# CCM_0020_revC.net
KiCad netlist of a schematic drawn in EAGLE
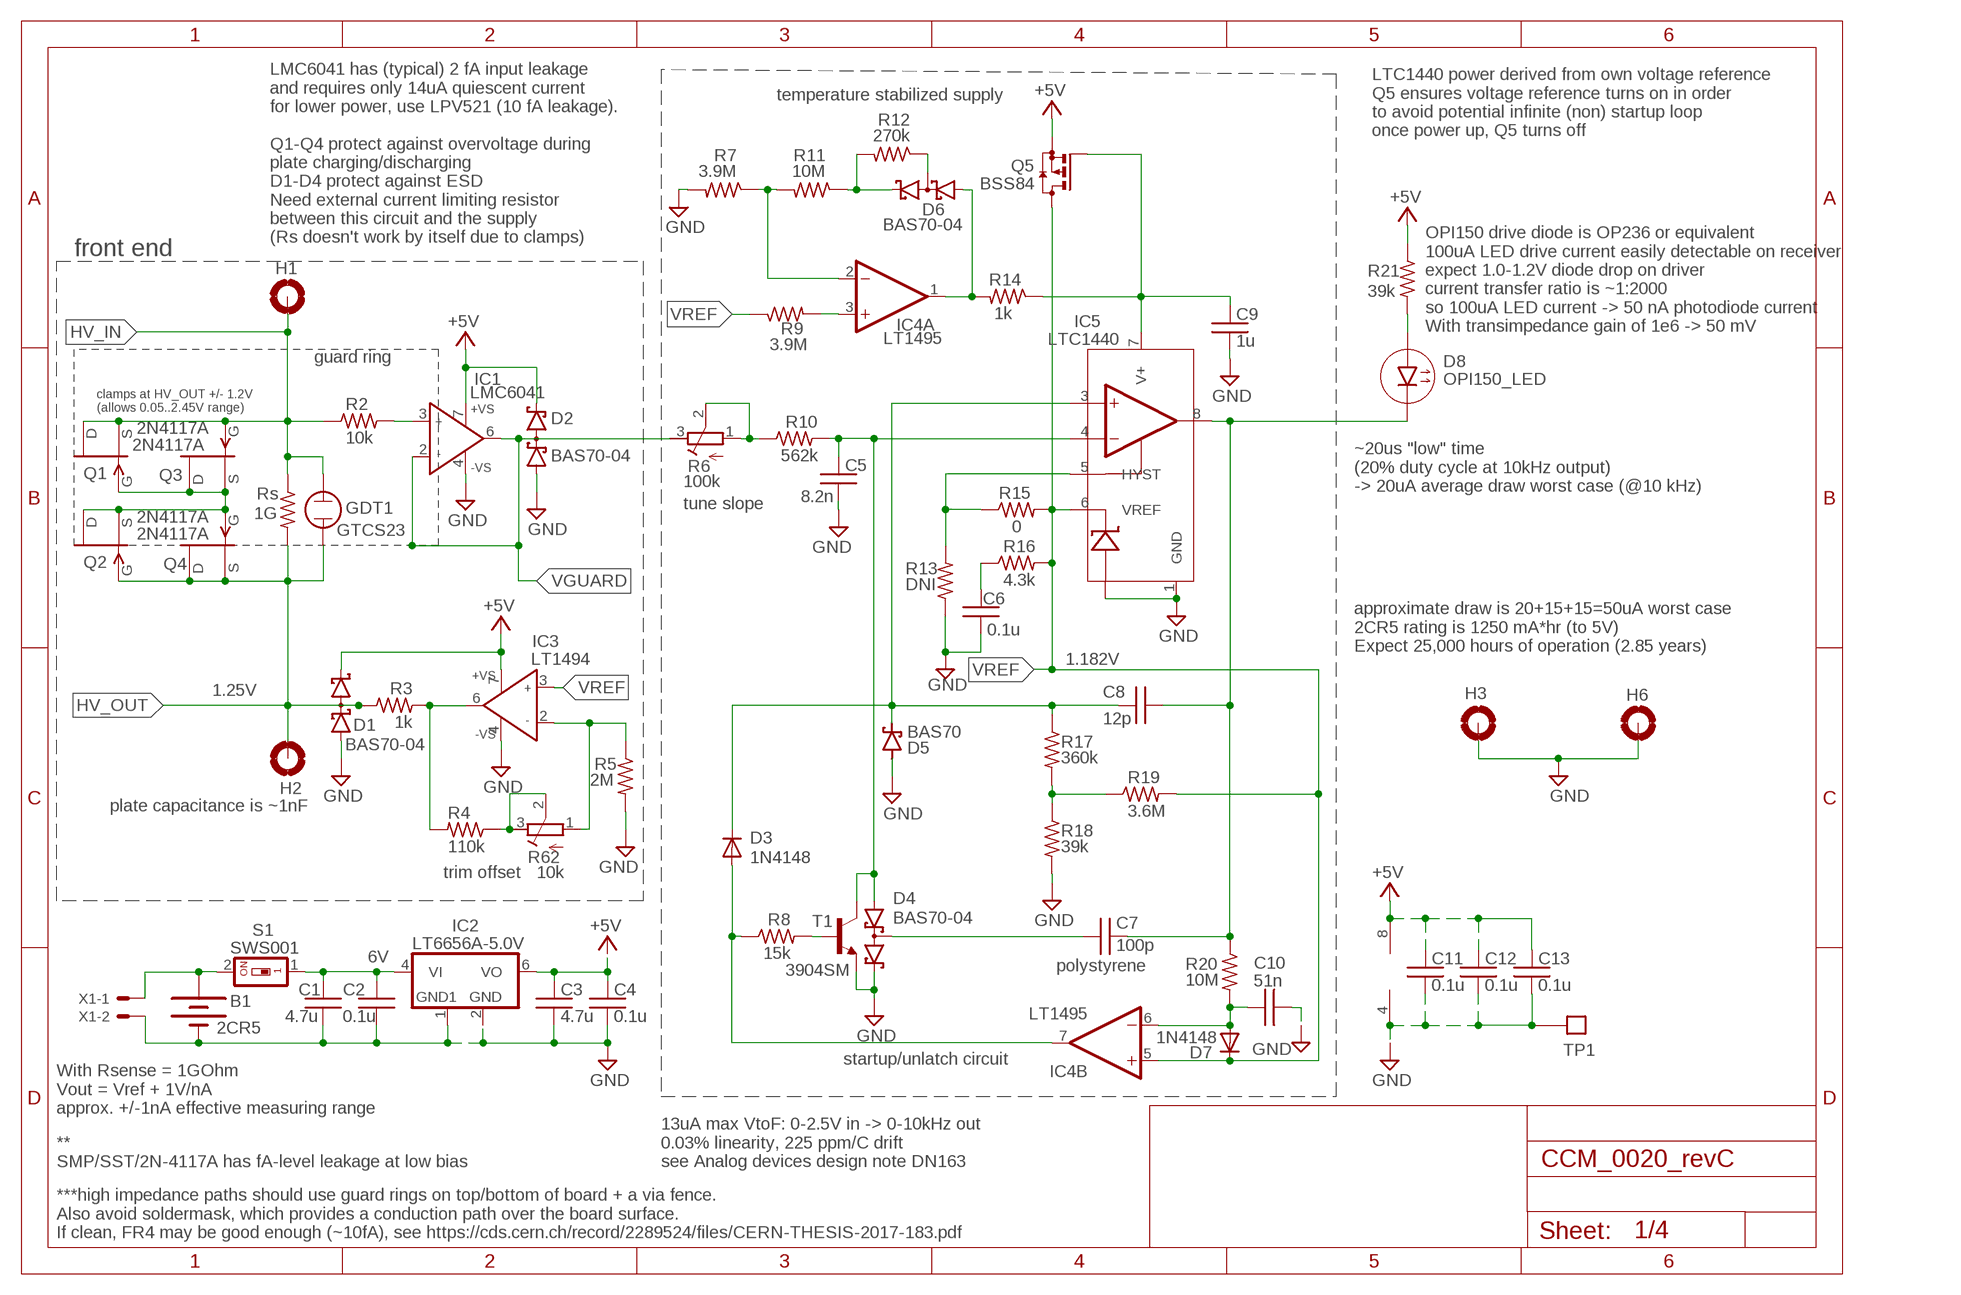
[diagram p0: schematic, sheet 1]
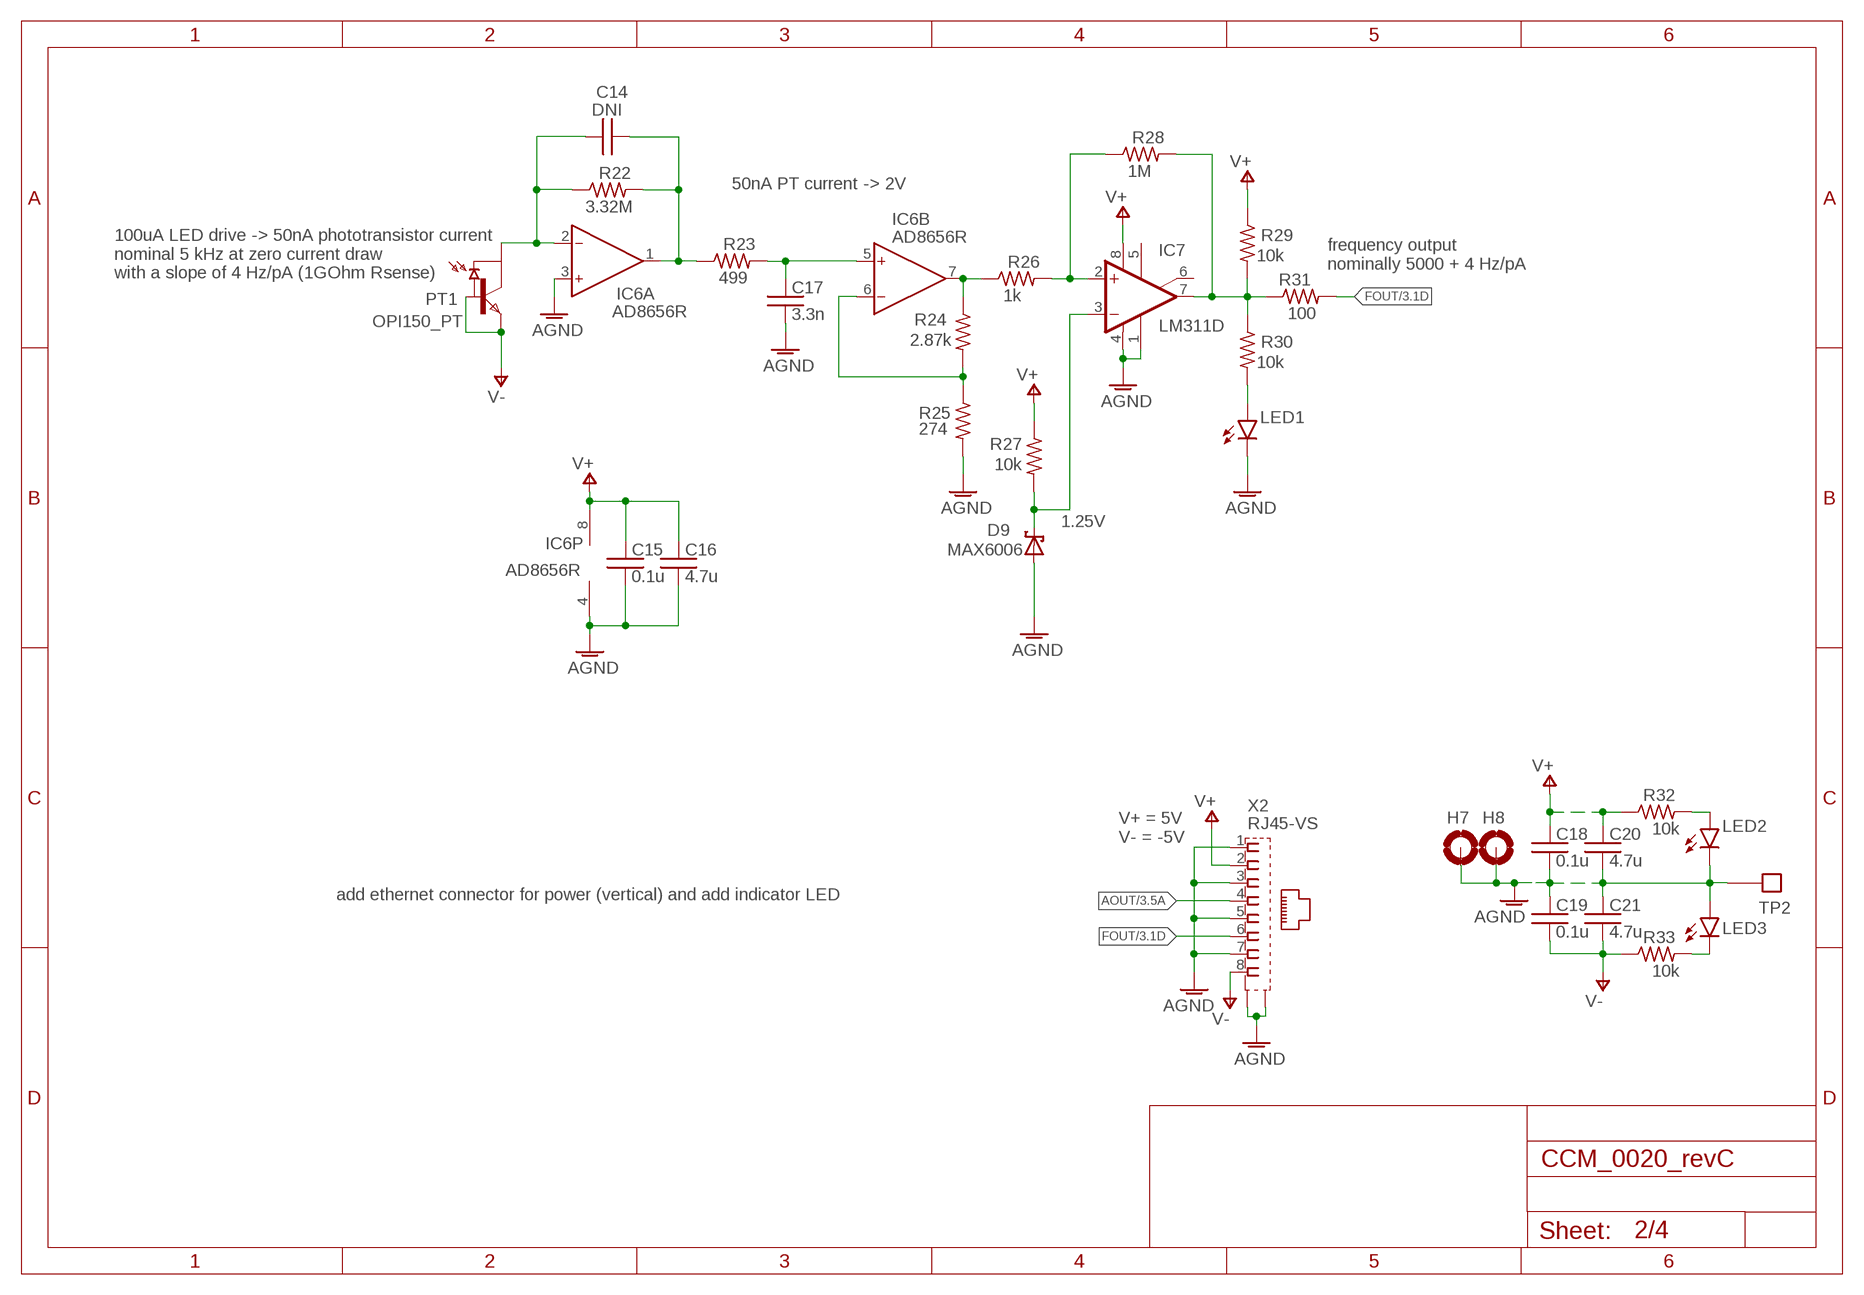
[diagram p1: schematic, sheet 2]
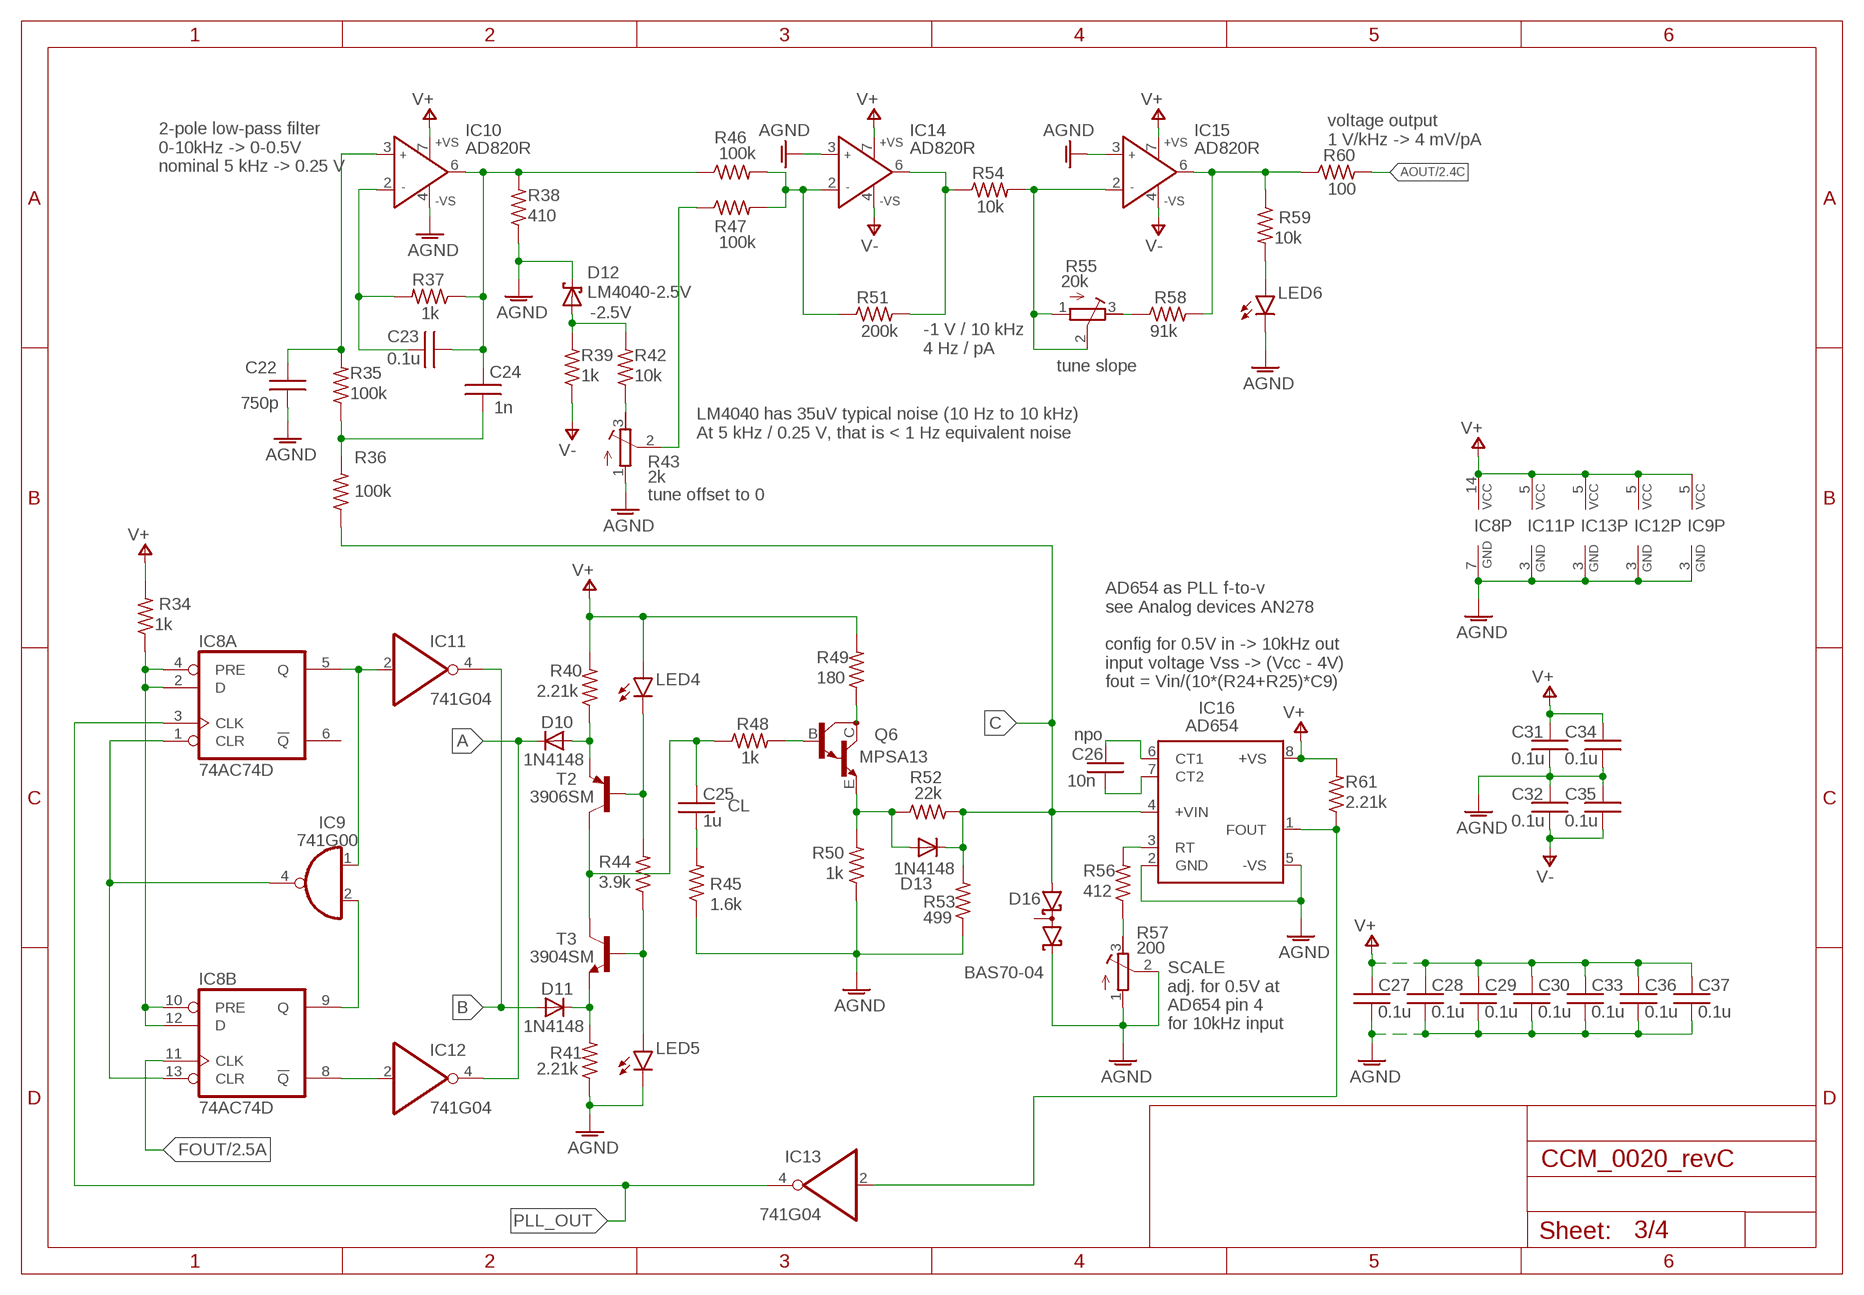
[diagram p2: schematic, sheet 3]
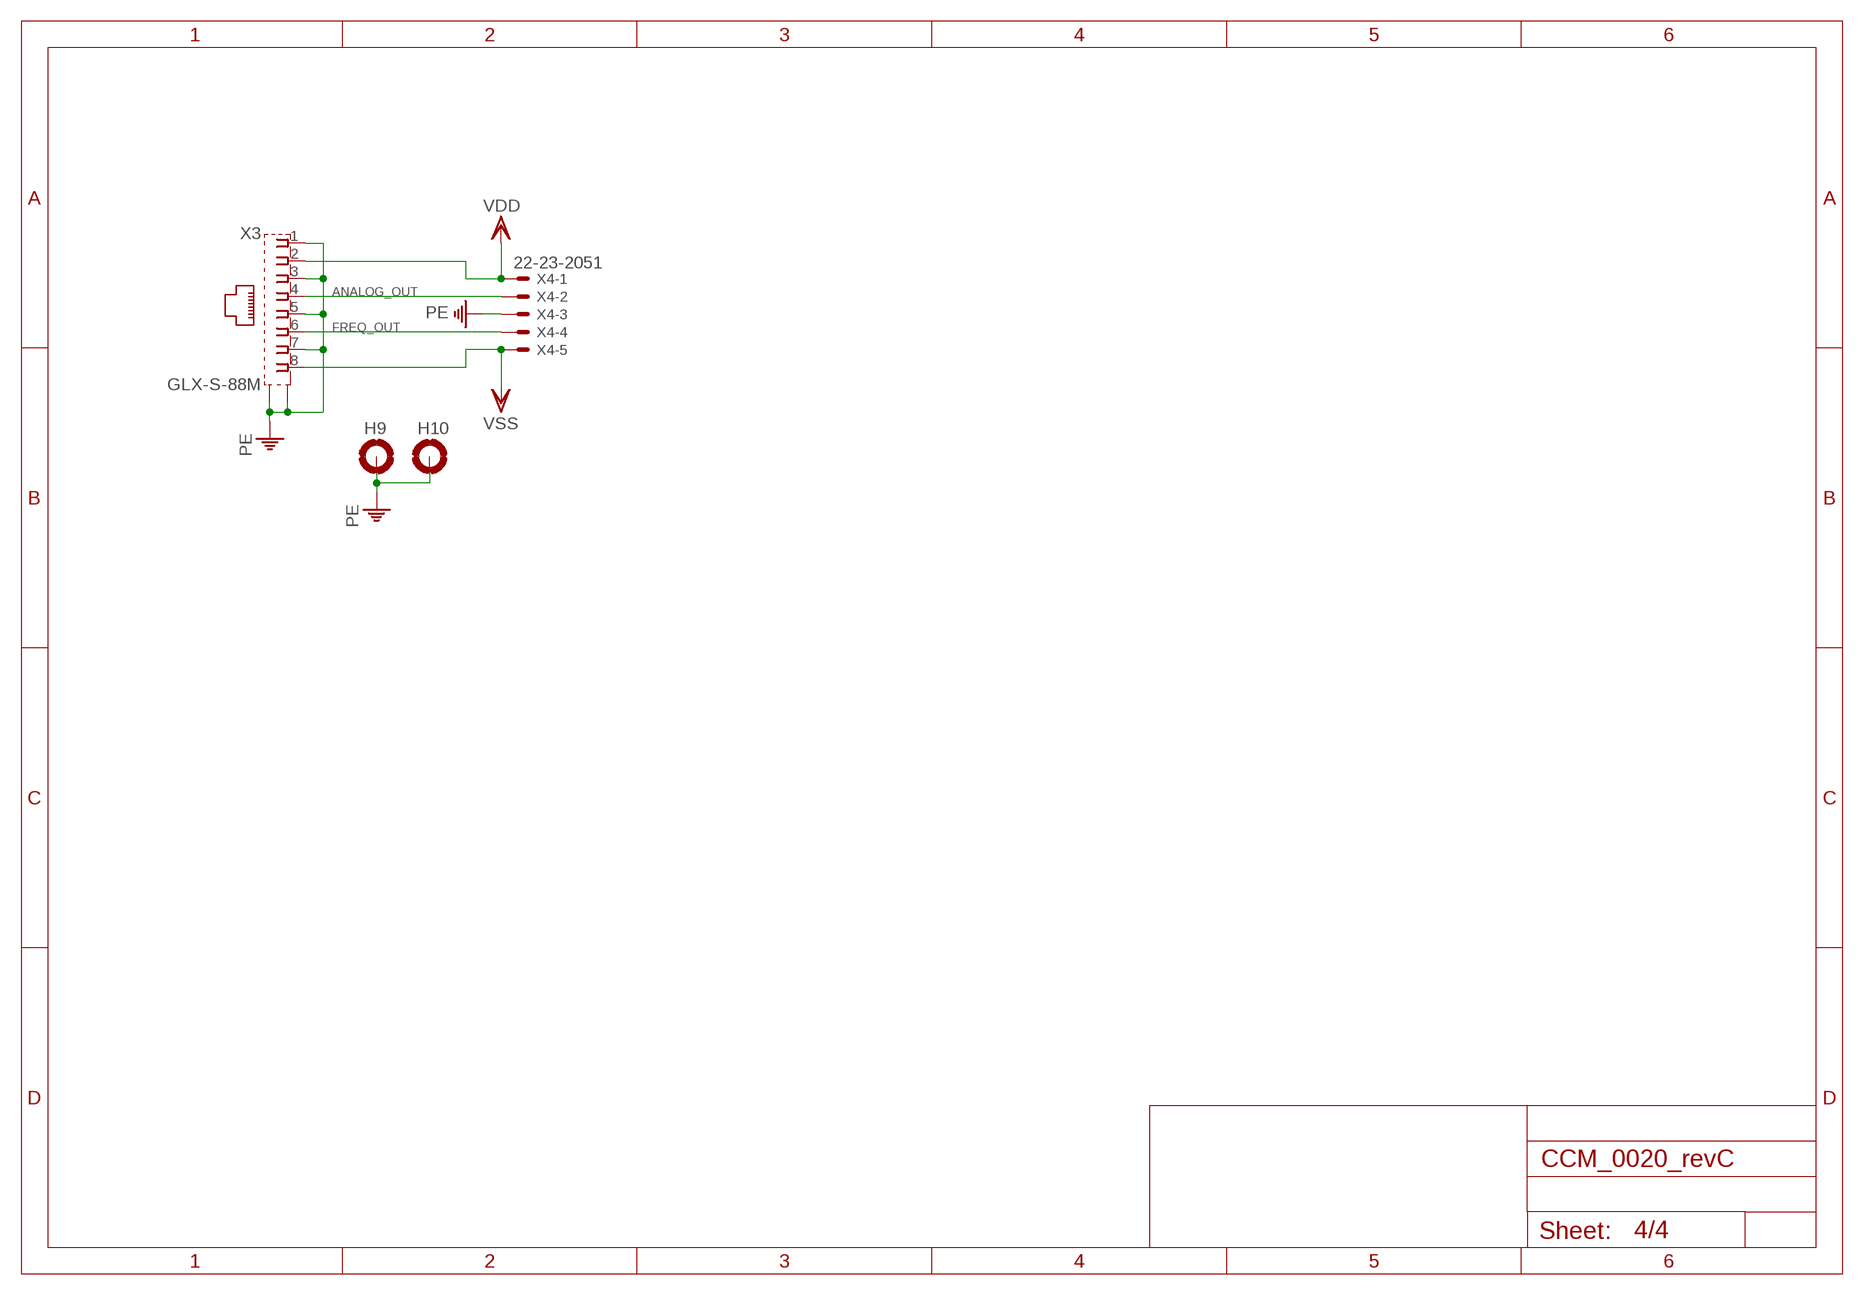
[diagram p3: schematic, sheet 4]

(export (version "E")
  (design (tool "Eeschema 10.0.6"))
  (components
    (comp (ref "B1")
      (value "2CR5")
      (footprint "eagle-import:2CR5")
      (libsource (lib "eagle-import") (part "BATTERY"))
    )
    (comp (ref "C1")
      (value "4.7u")
      (footprint "eagle-import:0603")
      (libsource (lib "eagle-import") (part "C0603"))
    )
    (comp (ref "C2")
      (value "0.1u")
      (footprint "eagle-import:0603")
      (libsource (lib "eagle-import") (part "C0603"))
    )
    (comp (ref "C3")
      (value "4.7u")
      (footprint "eagle-import:0603")
      (libsource (lib "eagle-import") (part "C0603"))
    )
    (comp (ref "C4")
      (value "0.1u")
      (footprint "eagle-import:0603")
      (libsource (lib "eagle-import") (part "C0603"))
    )
    (comp (ref "C5")
      (value "8.2n")
      (footprint "eagle-import:0603")
      (libsource (lib "eagle-import") (part "C0603"))
    )
    (comp (ref "C6")
      (value "0.1u")
      (footprint "eagle-import:0603")
      (libsource (lib "eagle-import") (part "C0603"))
    )
    (comp (ref "C7")
      (value "100p")
      (footprint "eagle-import:0603")
      (libsource (lib "eagle-import") (part "C0603"))
    )
    (comp (ref "C8")
      (value "12p")
      (footprint "eagle-import:0603")
      (libsource (lib "eagle-import") (part "C0603"))
    )
    (comp (ref "C9")
      (value "1u")
      (footprint "eagle-import:0603")
      (libsource (lib "eagle-import") (part "C0603"))
    )
    (comp (ref "C10")
      (value "51n")
      (footprint "eagle-import:0603")
      (libsource (lib "eagle-import") (part "C0603"))
    )
    (comp (ref "C11")
      (value "0.1u")
      (footprint "eagle-import:0603")
      (libsource (lib "eagle-import") (part "C0603"))
    )
    (comp (ref "C12")
      (value "0.1u")
      (footprint "eagle-import:0603")
      (libsource (lib "eagle-import") (part "C0603"))
    )
    (comp (ref "C13")
      (value "0.1u")
      (footprint "eagle-import:0603")
      (libsource (lib "eagle-import") (part "C0603"))
    )
    (comp (ref "D1")
      (value "BAS70-04")
      (footprint "eagle-import:SOT23")
      (libsource (lib "eagle-import") (part "BAS70-04"))
    )
    (comp (ref "D2")
      (value "BAS70-04")
      (footprint "eagle-import:SOT23")
      (libsource (lib "eagle-import") (part "BAS70-04"))
    )
    (comp (ref "D3")
      (value "1N4148")
      (footprint "eagle-import:SOD323_ST")
      (libsource (lib "eagle-import") (part "1N4148"))
    )
    (comp (ref "D4")
      (value "BAS70-04")
      (footprint "eagle-import:SOT23")
      (libsource (lib "eagle-import") (part "BAS70-04"))
    )
    (comp (ref "D5")
      (value "BAS70")
      (footprint "eagle-import:SOD323_ST")
      (libsource (lib "eagle-import") (part "BAT60J"))
    )
    (comp (ref "D6")
      (value "BAS70-04")
      (footprint "eagle-import:SOT23")
      (libsource (lib "eagle-import") (part "BAS70-04"))
    )
    (comp (ref "D7")
      (value "1N4148")
      (footprint "eagle-import:SOD323_ST")
      (libsource (lib "eagle-import") (part "1N4148"))
    )
    (comp (ref "D8")
      (value "OPI150_LED")
      (footprint "eagle-import:OPI150_LED")
      (libsource (lib "eagle-import") (part "OPI150_LED"))
    )
    (comp (ref "GDT1")
      (value "GTCS23")
      (footprint "eagle-import:GTCS23")
      (libsource (lib "eagle-import") (part "GTCS23"))
    )
    (comp (ref "H1")
      (value "MOUNT-PAD-ROUND3.0")
      (footprint "eagle-import:3,0-PAD")
      (libsource (lib "eagle-import") (part "MOUNT-PAD-ROUND3.0"))
    )
    (comp (ref "H2")
      (value "MOUNT-PAD-ROUND3.0")
      (footprint "eagle-import:3,0-PAD")
      (libsource (lib "eagle-import") (part "MOUNT-PAD-ROUND3.0"))
    )
    (comp (ref "H3")
      (value "MOUNT-PAD-ROUND3.0")
      (footprint "eagle-import:3,0-PAD")
      (libsource (lib "eagle-import") (part "MOUNT-PAD-ROUND3.0"))
    )
    (comp (ref "H6")
      (value "MOUNT-PAD-ROUND3.0")
      (footprint "eagle-import:3,0-PAD")
      (libsource (lib "eagle-import") (part "MOUNT-PAD-ROUND3.0"))
    )
    (comp (ref "IC1")
      (value "LMC6041")
      (footprint "eagle-import:SO8")
      (libsource (lib "eagle-import") (part "AD825_A"))
    )
    (comp (ref "IC2")
      (value "LT6656A-5.0V")
      (footprint "eagle-import:SOT23-6")
      (libsource (lib "eagle-import") (part "LT6656"))
    )
    (comp (ref "IC3")
      (value "LT1494")
      (footprint "eagle-import:SO8")
      (libsource (lib "eagle-import") (part "AD825_A"))
    )
    (comp (ref "IC4")
      (value "LT1495")
      (footprint "eagle-import:SO8")
      (libsource (lib "eagle-import") (part "LT1495D"))
    )
    (comp (ref "IC5")
      (value "LTC1440")
      (footprint "eagle-import:SO8")
      (libsource (lib "eagle-import") (part "LTC1440"))
    )
    (comp (ref "Q1")
      (value "2N4117A")
      (footprint "eagle-import:SOT23")
      (libsource (lib "eagle-import") (part "?548SST4"))
    )
    (comp (ref "Q2")
      (value "2N4117A")
      (footprint "eagle-import:SOT23")
      (libsource (lib "eagle-import") (part "?548SST4"))
    )
    (comp (ref "Q3")
      (value "2N4117A")
      (footprint "eagle-import:SOT23")
      (libsource (lib "eagle-import") (part "?548SST4"))
    )
    (comp (ref "Q4")
      (value "2N4117A")
      (footprint "eagle-import:SOT23")
      (libsource (lib "eagle-import") (part "?548SST4"))
    )
    (comp (ref "Q5")
      (value "BSS84")
      (footprint "eagle-import:SOT23")
      (libsource (lib "eagle-import") (part "BSS84"))
    )
    (comp (ref "R1")
      (value "1G")
      (footprint "eagle-import:2512")
      (libsource (lib "eagle-import") (part "RESISTOR2512"))
    )
    (comp (ref "R2")
      (value "10k")
      (footprint "eagle-import:0603")
      (libsource (lib "eagle-import") (part "R0603"))
    )
    (comp (ref "R3")
      (value "1k")
      (footprint "eagle-import:0603")
      (libsource (lib "eagle-import") (part "R0603"))
    )
    (comp (ref "R4")
      (value "110k")
      (footprint "eagle-import:0603")
      (libsource (lib "eagle-import") (part "R0603"))
    )
    (comp (ref "R5")
      (value "2M")
      (footprint "eagle-import:0603")
      (libsource (lib "eagle-import") (part "R0603"))
    )
    (comp (ref "R6")
      (value "100k")
      (footprint "eagle-import:RTRIM3224W")
      (libsource (lib "eagle-import") (part "R-TRIMM3224W"))
    )
    (comp (ref "R7")
      (value "3.9M")
      (footprint "eagle-import:0603")
      (libsource (lib "eagle-import") (part "R0603"))
    )
    (comp (ref "R8")
      (value "15k")
      (footprint "eagle-import:0603")
      (libsource (lib "eagle-import") (part "R0603"))
    )
    (comp (ref "R9")
      (value "3.9M")
      (footprint "eagle-import:0603")
      (libsource (lib "eagle-import") (part "R0603"))
    )
    (comp (ref "R10")
      (value "562k")
      (footprint "eagle-import:0603")
      (libsource (lib "eagle-import") (part "R0603"))
    )
    (comp (ref "R11")
      (value "10M")
      (footprint "eagle-import:0603")
      (libsource (lib "eagle-import") (part "R0603"))
    )
    (comp (ref "R12")
      (value "270k")
      (footprint "eagle-import:0603")
      (libsource (lib "eagle-import") (part "R0603"))
    )
    (comp (ref "R13")
      (value "DNI")
      (footprint "eagle-import:0603")
      (libsource (lib "eagle-import") (part "R0603"))
    )
    (comp (ref "R14")
      (value "1k")
      (footprint "eagle-import:0603")
      (libsource (lib "eagle-import") (part "R0603"))
    )
    (comp (ref "R15")
      (value "0")
      (footprint "eagle-import:0603")
      (libsource (lib "eagle-import") (part "R0603"))
    )
    (comp (ref "R16")
      (value "4.3k")
      (footprint "eagle-import:0603")
      (libsource (lib "eagle-import") (part "R0603"))
    )
    (comp (ref "R17")
      (value "360k")
      (footprint "eagle-import:0603")
      (libsource (lib "eagle-import") (part "R0603"))
    )
    (comp (ref "R18")
      (value "39k")
      (footprint "eagle-import:0603")
      (libsource (lib "eagle-import") (part "R0603"))
    )
    (comp (ref "R19")
      (value "3.6M")
      (footprint "eagle-import:0603")
      (libsource (lib "eagle-import") (part "R0603"))
    )
    (comp (ref "R20")
      (value "10M")
      (footprint "eagle-import:0603")
      (libsource (lib "eagle-import") (part "R0603"))
    )
    (comp (ref "R21")
      (value "39k")
      (footprint "eagle-import:0603")
      (libsource (lib "eagle-import") (part "R0603"))
    )
    (comp (ref "R62")
      (value "10k")
      (footprint "eagle-import:RTRIM3224W")
      (libsource (lib "eagle-import") (part "R-TRIMM3224W"))
    )
    (comp (ref "S1")
      (value "SWS001")
      (footprint "eagle-import:SMS-001")
      (libsource (lib "eagle-import") (part "SWS001"))
    )
    (comp (ref "T1")
      (value "3904SM")
      (footprint "eagle-import:SOT23")
      (libsource (lib "eagle-import") (part "3904SM"))
    )
    (comp (ref "TP1")
      (value "TESTPOINT")
      (footprint "eagle-import:TESTPOINT")
      (libsource (lib "eagle-import") (part "TESTPOINT"))
    )
    (comp (ref "X1")
      (value "22-23-2021")
      (footprint "eagle-import:22-23-2021")
      (fields (field (name "MF") "MOLEX"))
      (libsource (lib "eagle-import") (part "22-23-2021"))
    )
    (comp (ref "C22")
      (value "750p")
      (footprint "eagle-import:0603")
      (libsource (lib "eagle-import") (part "C0603"))
    )
    (comp (ref "C23")
      (value "0.1u")
      (footprint "eagle-import:0603")
      (libsource (lib "eagle-import") (part "C0603"))
    )
    (comp (ref "C24")
      (value "1n")
      (footprint "eagle-import:0603")
      (libsource (lib "eagle-import") (part "C0603"))
    )
    (comp (ref "C25")
      (value "1u")
      (footprint "eagle-import:0603")
      (libsource (lib "eagle-import") (part "C0603"))
    )
    (comp (ref "C26")
      (value "10n")
      (footprint "eagle-import:0603")
      (libsource (lib "eagle-import") (part "C0603"))
    )
    (comp (ref "C27")
      (value "0.1u")
      (footprint "eagle-import:0603")
      (libsource (lib "eagle-import") (part "C0603"))
    )
    (comp (ref "C28")
      (value "0.1u")
      (footprint "eagle-import:0603")
      (libsource (lib "eagle-import") (part "C0603"))
    )
    (comp (ref "C29")
      (value "0.1u")
      (footprint "eagle-import:0603")
      (libsource (lib "eagle-import") (part "C0603"))
    )
    (comp (ref "C30")
      (value "0.1u")
      (footprint "eagle-import:0603")
      (libsource (lib "eagle-import") (part "C0603"))
    )
    (comp (ref "C31")
      (value "0.1u")
      (footprint "eagle-import:0603")
      (libsource (lib "eagle-import") (part "C0603"))
    )
    (comp (ref "C32")
      (value "0.1u")
      (footprint "eagle-import:0603")
      (libsource (lib "eagle-import") (part "C0603"))
    )
    (comp (ref "C33")
      (value "0.1u")
      (footprint "eagle-import:0603")
      (libsource (lib "eagle-import") (part "C0603"))
    )
    (comp (ref "C34")
      (value "0.1u")
      (footprint "eagle-import:0603")
      (libsource (lib "eagle-import") (part "C0603"))
    )
    (comp (ref "C35")
      (value "0.1u")
      (footprint "eagle-import:0603")
      (libsource (lib "eagle-import") (part "C0603"))
    )
    (comp (ref "C36")
      (value "0.1u")
      (footprint "eagle-import:0603")
      (libsource (lib "eagle-import") (part "C0603"))
    )
    (comp (ref "C37")
      (value "0.1u")
      (footprint "eagle-import:0603")
      (libsource (lib "eagle-import") (part "C0603"))
    )
    (comp (ref "D10")
      (value "1N4148")
      (footprint "eagle-import:SOD323_ST")
      (libsource (lib "eagle-import") (part "1N4148"))
    )
    (comp (ref "D11")
      (value "1N4148")
      (footprint "eagle-import:SOD323_ST")
      (libsource (lib "eagle-import") (part "1N4148"))
    )
    (comp (ref "D12")
      (value "LM4040-2.5V")
      (footprint "eagle-import:SOT23")
      (libsource (lib "eagle-import") (part "LM4040"))
    )
    (comp (ref "D13")
      (value "1N4148")
      (footprint "eagle-import:SOD323_ST")
      (libsource (lib "eagle-import") (part "1N4148"))
    )
    (comp (ref "D16")
      (value "BAS70-04")
      (footprint "eagle-import:SOT23")
      (libsource (lib "eagle-import") (part "BAS70-04"))
    )
    (comp (ref "IC8")
      (value "74AC74D")
      (footprint "eagle-import:SO14")
      (libsource (lib "eagle-import") (part "7474DAC"))
    )
    (comp (ref "IC9")
      (value "741G00")
      (footprint "eagle-import:SOT23-5")
      (libsource (lib "eagle-import") (part "741G00DBVAHC"))
    )
    (comp (ref "IC10")
      (value "AD820R")
      (footprint "eagle-import:SO8")
      (libsource (lib "eagle-import") (part "AD820R"))
    )
    (comp (ref "IC11")
      (value "741G04")
      (footprint "eagle-import:SOT23-5")
      (libsource (lib "eagle-import") (part "741G04DBVAHC"))
    )
    (comp (ref "IC12")
      (value "741G04")
      (footprint "eagle-import:SOT23-5")
      (libsource (lib "eagle-import") (part "741G04DBVAHC"))
    )
    (comp (ref "IC13")
      (value "741G04")
      (footprint "eagle-import:SOT23-5")
      (libsource (lib "eagle-import") (part "741G04DBVAHC"))
    )
    (comp (ref "IC14")
      (value "AD820R")
      (footprint "eagle-import:SO8")
      (libsource (lib "eagle-import") (part "AD820R"))
    )
    (comp (ref "IC15")
      (value "AD820R")
      (footprint "eagle-import:SO8")
      (libsource (lib "eagle-import") (part "AD820R"))
    )
    (comp (ref "IC16")
      (value "AD654")
      (footprint "eagle-import:SO08")
      (libsource (lib "eagle-import") (part "AD654"))
    )
    (comp (ref "LED4")
      (value "LEDCHIP-LED0603")
      (footprint "eagle-import:CHIP-LED0603")
      (libsource (lib "eagle-import") (part "LEDCHIP-LED0603"))
    )
    (comp (ref "LED5")
      (value "LEDCHIP-LED0603")
      (footprint "eagle-import:CHIP-LED0603")
      (libsource (lib "eagle-import") (part "LEDCHIP-LED0603"))
    )
    (comp (ref "LED6")
      (value "LEDCHIP-LED0603")
      (footprint "eagle-import:CHIP-LED0603")
      (libsource (lib "eagle-import") (part "LEDCHIP-LED0603"))
    )
    (comp (ref "Q6")
      (value "MPSA13")
      (footprint "eagle-import:SOT23-BEC")
      (libsource (lib "eagle-import") (part "MMBTA13LT1"))
    )
    (comp (ref "R34")
      (value "1k")
      (footprint "eagle-import:0603")
      (libsource (lib "eagle-import") (part "R0603"))
    )
    (comp (ref "R35")
      (value "100k")
      (footprint "eagle-import:0603")
      (libsource (lib "eagle-import") (part "R0603"))
    )
    (comp (ref "R36")
      (value "100k")
      (footprint "eagle-import:0603")
      (libsource (lib "eagle-import") (part "R0603"))
    )
    (comp (ref "R37")
      (value "1k")
      (footprint "eagle-import:0603")
      (libsource (lib "eagle-import") (part "R0603"))
    )
    (comp (ref "R38")
      (value "410")
      (footprint "eagle-import:0603")
      (libsource (lib "eagle-import") (part "R0603"))
    )
    (comp (ref "R39")
      (value "1k")
      (footprint "eagle-import:0603")
      (libsource (lib "eagle-import") (part "R0603"))
    )
    (comp (ref "R40")
      (value "2.21k")
      (footprint "eagle-import:0603")
      (libsource (lib "eagle-import") (part "R0603"))
    )
    (comp (ref "R41")
      (value "2.21k")
      (footprint "eagle-import:0603")
      (libsource (lib "eagle-import") (part "R0603"))
    )
    (comp (ref "R42")
      (value "10k")
      (footprint "eagle-import:0603")
      (libsource (lib "eagle-import") (part "R0603"))
    )
    (comp (ref "R43")
      (value "2k")
      (footprint "eagle-import:RTRIM3224W")
      (libsource (lib "eagle-import") (part "R-TRIMM3224W"))
    )
    (comp (ref "R44")
      (value "3.9k")
      (footprint "eagle-import:0603")
      (libsource (lib "eagle-import") (part "R0603"))
    )
    (comp (ref "R45")
      (value "1.6k")
      (footprint "eagle-import:0603")
      (libsource (lib "eagle-import") (part "R0603"))
    )
    (comp (ref "R46")
      (value "100k")
      (footprint "eagle-import:0603")
      (libsource (lib "eagle-import") (part "R0603"))
    )
    (comp (ref "R47")
      (value "100k")
      (footprint "eagle-import:0603")
      (libsource (lib "eagle-import") (part "R0603"))
    )
    (comp (ref "R48")
      (value "1k")
      (footprint "eagle-import:0603")
      (libsource (lib "eagle-import") (part "R0603"))
    )
    (comp (ref "R49")
      (value "180")
      (footprint "eagle-import:0603")
      (libsource (lib "eagle-import") (part "R0603"))
    )
    (comp (ref "R50")
      (value "1k")
      (footprint "eagle-import:0603")
      (libsource (lib "eagle-import") (part "R0603"))
    )
    (comp (ref "R51")
      (value "200k")
      (footprint "eagle-import:0603")
      (libsource (lib "eagle-import") (part "R0603"))
    )
    (comp (ref "R52")
      (value "22k")
      (footprint "eagle-import:0603")
      (libsource (lib "eagle-import") (part "R0603"))
    )
    (comp (ref "R53")
      (value "499")
      (footprint "eagle-import:0603")
      (libsource (lib "eagle-import") (part "R0603"))
    )
    (comp (ref "R54")
      (value "10k")
      (footprint "eagle-import:0603")
      (libsource (lib "eagle-import") (part "R0603"))
    )
    (comp (ref "R55")
      (value "20k")
      (footprint "eagle-import:RTRIM3224W")
      (libsource (lib "eagle-import") (part "R-TRIMM3224W"))
    )
    (comp (ref "R56")
      (value "412")
      (footprint "eagle-import:0603")
      (libsource (lib "eagle-import") (part "R0603"))
    )
    (comp (ref "R57")
      (value "200")
      (footprint "eagle-import:RTRIM3224W")
      (libsource (lib "eagle-import") (part "R-TRIMM3224W"))
    )
    (comp (ref "R58")
      (value "91k")
      (footprint "eagle-import:0603")
      (libsource (lib "eagle-import") (part "R0603"))
    )
    (comp (ref "R59")
      (value "10k")
      (footprint "eagle-import:0603")
      (libsource (lib "eagle-import") (part "R0603"))
    )
    (comp (ref "R60")
      (value "100")
      (footprint "eagle-import:0603")
      (libsource (lib "eagle-import") (part "R0603"))
    )
    (comp (ref "R61")
      (value "2.21k")
      (footprint "eagle-import:0603")
      (libsource (lib "eagle-import") (part "R0603"))
    )
    (comp (ref "T2")
      (value "3906SM")
      (footprint "eagle-import:SOT23-BEC")
      (libsource (lib "eagle-import") (part "-PNP-SOT23-BECMMBT3906LT1"))
    )
    (comp (ref "T3")
      (value "3904SM")
      (footprint "eagle-import:SOT23")
      (libsource (lib "eagle-import") (part "3904SM"))
    )
    (comp (ref "H9")
      (value "MOUNT-PAD-ROUND3.0")
      (footprint "eagle-import:3,0-PAD")
      (libsource (lib "eagle-import") (part "MOUNT-PAD-ROUND3.0"))
    )
    (comp (ref "H10")
      (value "MOUNT-PAD-ROUND3.0")
      (footprint "eagle-import:3,0-PAD")
      (libsource (lib "eagle-import") (part "MOUNT-PAD-ROUND3.0"))
    )
    (comp (ref "X3")
      (value "GLX-S-88M")
      (footprint "eagle-import:GLX-S-88M")
      (libsource (lib "eagle-import") (part "GLX-S-88M"))
    )
    (comp (ref "X4")
      (value "22-23-2051")
      (footprint "eagle-import:22-23-2051")
      (fields (field (name "MF") "MOLEX"))
      (libsource (lib "eagle-import") (part "22-23-2051"))
    )
    (comp (ref "C14")
      (value "DNI")
      (footprint "eagle-import:0603")
      (libsource (lib "eagle-import") (part "C0603"))
    )
    (comp (ref "C15")
      (value "0.1u")
      (footprint "eagle-import:0603")
      (libsource (lib "eagle-import") (part "C0603"))
    )
    (comp (ref "C16")
      (value "4.7u")
      (footprint "eagle-import:0603")
      (libsource (lib "eagle-import") (part "C0603"))
    )
    (comp (ref "C17")
      (value "3.3n")
      (footprint "eagle-import:0603")
      (libsource (lib "eagle-import") (part "C0603"))
    )
    (comp (ref "C18")
      (value "0.1u")
      (footprint "eagle-import:0603")
      (libsource (lib "eagle-import") (part "C0603"))
    )
    (comp (ref "C19")
      (value "0.1u")
      (footprint "eagle-import:0603")
      (libsource (lib "eagle-import") (part "C0603"))
    )
    (comp (ref "C20")
      (value "4.7u")
      (footprint "eagle-import:0603")
      (libsource (lib "eagle-import") (part "C0603"))
    )
    (comp (ref "C21")
      (value "4.7u")
      (footprint "eagle-import:0603")
      (libsource (lib "eagle-import") (part "C0603"))
    )
    (comp (ref "D9")
      (value "MAX6006")
      (footprint "eagle-import:SOT23")
      (libsource (lib "eagle-import") (part "LM4040"))
    )
    (comp (ref "H7")
      (value "MOUNT-PAD-ROUND3.0")
      (footprint "eagle-import:3,0-PAD")
      (libsource (lib "eagle-import") (part "MOUNT-PAD-ROUND3.0"))
    )
    (comp (ref "H8")
      (value "MOUNT-PAD-ROUND3.0")
      (footprint "eagle-import:3,0-PAD")
      (libsource (lib "eagle-import") (part "MOUNT-PAD-ROUND3.0"))
    )
    (comp (ref "IC6")
      (value "AD8656R")
      (footprint "eagle-import:SO8")
      (fields (field (name "MPN") "AD8656ARZ"))
      (libsource (lib "eagle-import") (part "AD8656R"))
    )
    (comp (ref "IC7")
      (value "LM311D")
      (footprint "eagle-import:SO08")
      (libsource (lib "eagle-import") (part "LM311D"))
    )
    (comp (ref "LED1")
      (value "LEDCHIP-LED0603")
      (footprint "eagle-import:CHIP-LED0603")
      (libsource (lib "eagle-import") (part "LEDCHIP-LED0603"))
    )
    (comp (ref "LED2")
      (value "LEDCHIP-LED0603")
      (footprint "eagle-import:CHIP-LED0603")
      (libsource (lib "eagle-import") (part "LEDCHIP-LED0603"))
    )
    (comp (ref "LED3")
      (value "LEDCHIP-LED0603")
      (footprint "eagle-import:CHIP-LED0603")
      (libsource (lib "eagle-import") (part "LEDCHIP-LED0603"))
    )
    (comp (ref "PT1")
      (value "OPI150_PT")
      (footprint "eagle-import:OPI150_PHOTOTRANSISTOR")
      (libsource (lib "eagle-import") (part "OPI150_PHOTOTRANSISTOR"))
    )
    (comp (ref "R22")
      (value "3.32M")
      (footprint "eagle-import:0603")
      (libsource (lib "eagle-import") (part "R0603"))
    )
    (comp (ref "R23")
      (value "499")
      (footprint "eagle-import:0603")
      (libsource (lib "eagle-import") (part "R0603"))
    )
    (comp (ref "R24")
      (value "2.87k")
      (footprint "eagle-import:0603")
      (libsource (lib "eagle-import") (part "R0603"))
    )
    (comp (ref "R25")
      (value "274")
      (footprint "eagle-import:0603")
      (libsource (lib "eagle-import") (part "R0603"))
    )
    (comp (ref "R26")
      (value "1k")
      (footprint "eagle-import:0603")
      (libsource (lib "eagle-import") (part "R0603"))
    )
    (comp (ref "R27")
      (value "10k")
      (footprint "eagle-import:0603")
      (libsource (lib "eagle-import") (part "R0603"))
    )
    (comp (ref "R28")
      (value "1M")
      (footprint "eagle-import:0603")
      (libsource (lib "eagle-import") (part "R0603"))
    )
    (comp (ref "R29")
      (value "10k")
      (footprint "eagle-import:0603")
      (libsource (lib "eagle-import") (part "R0603"))
    )
    (comp (ref "R30")
      (value "10k")
      (footprint "eagle-import:0603")
      (libsource (lib "eagle-import") (part "R0603"))
    )
    (comp (ref "R31")
      (value "100")
      (footprint "eagle-import:0603")
      (libsource (lib "eagle-import") (part "R0603"))
    )
    (comp (ref "R32")
      (value "10k")
      (footprint "eagle-import:0603")
      (libsource (lib "eagle-import") (part "R0603"))
    )
    (comp (ref "R33")
      (value "10k")
      (footprint "eagle-import:0603")
      (libsource (lib "eagle-import") (part "R0603"))
    )
    (comp (ref "TP2")
      (value "TESTPOINT")
      (footprint "eagle-import:TESTPOINT")
      (libsource (lib "eagle-import") (part "TESTPOINT"))
    )
    (comp (ref "X2")
      (value "RJ45-VS")
      (footprint "eagle-import:RJ45-VS")
      (libsource (lib "eagle-import") (part "RJ45-VS"))
    )
  )
  (nets
    (net (code "1") (name "+5V") (class "Default")
      (node (ref "C11") (pin "1") (pinfunction "1_1") (pintype "passive"))
      (node (ref "C12") (pin "1") (pinfunction "1_1") (pintype "passive"))
      (node (ref "C13") (pin "1") (pinfunction "1_1") (pintype "passive"))
      (node (ref "C3") (pin "1") (pinfunction "1_1") (pintype "passive"))
      (node (ref "C4") (pin "1") (pinfunction "1_1") (pintype "passive"))
      (node (ref "D1") (pin "2") (pinfunction "C2_2") (pintype "passive"))
      (node (ref "D2") (pin "2") (pinfunction "C2_2") (pintype "passive"))
      (node (ref "IC1") (pin "7") (pinfunction "+VS_7") (pintype "input"))
      (node (ref "IC2") (pin "6") (pinfunction "VO_6") (pintype "passive"))
      (node (ref "IC3") (pin "7") (pinfunction "+VS_7") (pintype "input"))
      (node (ref "IC4") (pin "8") (pinfunction "V+_8") (pintype "power_in"))
      (node (ref "Q5") (pin "2") (pinfunction "S_2") (pintype "passive"))
      (node (ref "R21") (pin "1") (pinfunction "1_1") (pintype "passive"))
    )
    (net (code "2") (name "A") (class "Default")
      (node (ref "D10") (pin "C") (pinfunction "C_C") (pintype "passive"))
      (node (ref "IC12") (pin "4") (pinfunction "O_4") (pintype "output"))
    )
    (net (code "3") (name "AGND") (class "Default")
      (node (ref "C15") (pin "2") (pinfunction "2_2") (pintype "passive"))
      (node (ref "C16") (pin "2") (pinfunction "2_2") (pintype "passive"))
      (node (ref "C17") (pin "2") (pinfunction "2_2") (pintype "passive"))
      (node (ref "C18") (pin "2") (pinfunction "2_2") (pintype "passive"))
      (node (ref "C19") (pin "1") (pinfunction "1_1") (pintype "passive"))
      (node (ref "C20") (pin "2") (pinfunction "2_2") (pintype "passive"))
      (node (ref "C21") (pin "1") (pinfunction "1_1") (pintype "passive"))
      (node (ref "C22") (pin "1") (pinfunction "1_1") (pintype "passive"))
      (node (ref "C27") (pin "2") (pinfunction "2_2") (pintype "passive"))
      (node (ref "C28") (pin "2") (pinfunction "2_2") (pintype "passive"))
      (node (ref "C29") (pin "2") (pinfunction "2_2") (pintype "passive"))
      (node (ref "C30") (pin "2") (pinfunction "2_2") (pintype "passive"))
      (node (ref "C31") (pin "1") (pinfunction "1_1") (pintype "passive"))
      (node (ref "C32") (pin "2") (pinfunction "2_2") (pintype "passive"))
      (node (ref "C33") (pin "2") (pinfunction "2_2") (pintype "passive"))
      (node (ref "C34") (pin "1") (pinfunction "1_1") (pintype "passive"))
      (node (ref "C35") (pin "2") (pinfunction "2_2") (pintype "passive"))
      (node (ref "C36") (pin "2") (pinfunction "2_2") (pintype "passive"))
      (node (ref "C37") (pin "2") (pinfunction "2_2") (pintype "passive"))
      (node (ref "D12") (pin "1") (pinfunction "C_1") (pintype "passive"))
      (node (ref "D16") (pin "2") (pinfunction "C2_2") (pintype "passive"))
      (node (ref "D9") (pin "2") (pinfunction "A_2") (pintype "passive"))
      (node (ref "H7") (pin "B3,0") (pinfunction "MOUNT_B3,0") (pintype "passive"))
      (node (ref "H8") (pin "B3,0") (pinfunction "MOUNT_B3,0") (pintype "passive"))
      (node (ref "IC10") (pin "4") (pinfunction "-VS_4") (pintype "input"))
      (node (ref "IC11") (pin "3") (pinfunction "GND_3") (pintype "power_in"))
      (node (ref "IC12") (pin "3") (pinfunction "GND_3") (pintype "power_in"))
      (node (ref "IC13") (pin "3") (pinfunction "GND_3") (pintype "power_in"))
      (node (ref "IC14") (pin "3") (pinfunction "IN+_3") (pintype "input"))
      (node (ref "IC15") (pin "3") (pinfunction "IN+_3") (pintype "input"))
      (node (ref "IC16") (pin "2") (pinfunction "GND_2") (pintype "power_in"))
      (node (ref "IC16") (pin "5") (pinfunction "-VS_5") (pintype "power_in"))
      (node (ref "IC6") (pin "3") (pinfunction "IN+_3") (pintype "input"))
      (node (ref "IC6") (pin "4") (pinfunction "V-_4") (pintype "power_in"))
      (node (ref "IC7") (pin "1") (pinfunction "GND_1") (pintype "passive"))
      (node (ref "IC7") (pin "4") (pinfunction "V-_4") (pintype "power_in"))
      (node (ref "IC8") (pin "7") (pinfunction "GND_7") (pintype "power_in"))
      (node (ref "IC9") (pin "3") (pinfunction "GND_3") (pintype "power_in"))
      (node (ref "LED1") (pin "C") (pinfunction "C_C") (pintype "passive"))
      (node (ref "LED2") (pin "C") (pinfunction "C_C") (pintype "passive"))
      (node (ref "LED3") (pin "A") (pinfunction "A_A") (pintype "passive"))
      (node (ref "LED5") (pin "C") (pinfunction "C_C") (pintype "passive"))
      (node (ref "LED6") (pin "C") (pinfunction "C_C") (pintype "passive"))
      (node (ref "R25") (pin "2") (pinfunction "2_2") (pintype "passive"))
      (node (ref "R38") (pin "1") (pinfunction "1_1") (pintype "passive"))
      (node (ref "R41") (pin "1") (pinfunction "1_1") (pintype "passive"))
      (node (ref "R43") (pin "1") (pinfunction "A_1") (pintype "passive"))
      (node (ref "R45") (pin "1") (pinfunction "1_1") (pintype "passive"))
      (node (ref "R50") (pin "1") (pinfunction "1_1") (pintype "passive"))
      (node (ref "R53") (pin "1") (pinfunction "1_1") (pintype "passive"))
      (node (ref "R57") (pin "1") (pinfunction "A_1") (pintype "passive"))
      (node (ref "R57") (pin "2") (pinfunction "S_2") (pintype "passive"))
      (node (ref "TP2") (pin "P$1") (pinfunction "P$1_P$1") (pintype "bidirectional"))
      (node (ref "X2") (pin "1") (pinfunction "1_1") (pintype "passive"))
      (node (ref "X2") (pin "3") (pinfunction "3_3") (pintype "passive"))
      (node (ref "X2") (pin "5") (pinfunction "5_5") (pintype "passive"))
      (node (ref "X2") (pin "7") (pinfunction "7_7") (pintype "passive"))
      (node (ref "X2") (pin "S1") (pinfunction "S1_S1") (pintype "passive"))
      (node (ref "X2") (pin "S2") (pinfunction "S2_S2") (pintype "passive"))
    )
    (net (code "4") (name "ANALOG_OUT") (class "Default")
      (node (ref "X3") (pin "4") (pinfunction "4_4") (pintype "passive"))
      (node (ref "X4") (pin "2") (pinfunction "S_2") (pintype "passive"))
    )
    (net (code "5") (name "AOUT") (class "Default")
      (node (ref "R60") (pin "2") (pinfunction "2_2") (pintype "passive"))
      (node (ref "X2") (pin "4") (pinfunction "4_4") (pintype "passive"))
    )
    (net (code "6") (name "B") (class "Default")
      (node (ref "D11") (pin "A") (pinfunction "A_A") (pintype "passive"))
      (node (ref "IC11") (pin "4") (pinfunction "O_4") (pintype "output"))
    )
    (net (code "7") (name "C") (class "Default")
      (node (ref "D13") (pin "C") (pinfunction "C_C") (pintype "passive"))
      (node (ref "D16") (pin "1") (pinfunction "A1_1") (pintype "passive"))
      (node (ref "IC16") (pin "4") (pinfunction "+VIN_4") (pintype "input"))
      (node (ref "R36") (pin "1") (pinfunction "1_1") (pintype "passive"))
      (node (ref "R52") (pin "2") (pinfunction "2_2") (pintype "passive"))
      (node (ref "R53") (pin "2") (pinfunction "2_2") (pintype "passive"))
    )
    (net (code "8") (name "FOUT") (class "Default")
      (node (ref "IC8") (pin "11") (pinfunction "CLK_11") (pintype "input"))
      (node (ref "R31") (pin "2") (pinfunction "2_2") (pintype "passive"))
      (node (ref "X2") (pin "6") (pinfunction "6_6") (pintype "passive"))
    )
    (net (code "9") (name "FREQ_OUT") (class "Default")
      (node (ref "X3") (pin "6") (pinfunction "6_6") (pintype "passive"))
      (node (ref "X4") (pin "4") (pinfunction "S_4") (pintype "passive"))
    )
    (net (code "10") (name "GND") (class "Default")
      (node (ref "B1") (pin "V-") (pinfunction "-_V-") (pintype "power_in"))
      (node (ref "C1") (pin "2") (pinfunction "2_2") (pintype "passive"))
      (node (ref "C10") (pin "2") (pinfunction "2_2") (pintype "passive"))
      (node (ref "C11") (pin "2") (pinfunction "2_2") (pintype "passive"))
      (node (ref "C12") (pin "2") (pinfunction "2_2") (pintype "passive"))
      (node (ref "C13") (pin "2") (pinfunction "2_2") (pintype "passive"))
      (node (ref "C2") (pin "2") (pinfunction "2_2") (pintype "passive"))
      (node (ref "C3") (pin "2") (pinfunction "2_2") (pintype "passive"))
      (node (ref "C4") (pin "2") (pinfunction "2_2") (pintype "passive"))
      (node (ref "C5") (pin "2") (pinfunction "2_2") (pintype "passive"))
      (node (ref "C6") (pin "1") (pinfunction "1_1") (pintype "passive"))
      (node (ref "C9") (pin "2") (pinfunction "2_2") (pintype "passive"))
      (node (ref "D1") (pin "1") (pinfunction "A1_1") (pintype "passive"))
      (node (ref "D2") (pin "1") (pinfunction "A1_1") (pintype "passive"))
      (node (ref "D4") (pin "2") (pinfunction "C2_2") (pintype "passive"))
      (node (ref "D5") (pin "A") (pinfunction "A_A") (pintype "passive"))
      (node (ref "H3") (pin "B3,0") (pinfunction "MOUNT_B3,0") (pintype "passive"))
      (node (ref "H6") (pin "B3,0") (pinfunction "MOUNT_B3,0") (pintype "passive"))
      (node (ref "IC1") (pin "4") (pinfunction "-VS_4") (pintype "input"))
      (node (ref "IC2") (pin "1") (pinfunction "GND1_1") (pintype "passive"))
      (node (ref "IC2") (pin "2") (pinfunction "GND_2") (pintype "passive"))
      (node (ref "IC3") (pin "4") (pinfunction "-VS_4") (pintype "input"))
      (node (ref "IC4") (pin "4") (pinfunction "V-_4") (pintype "power_in"))
      (node (ref "IC5") (pin "1") (pinfunction "GND_1") (pintype "power_in"))
      (node (ref "IC5") (pin "2") (pinfunction "V-_2") (pintype "passive"))
      (node (ref "R13") (pin "1") (pinfunction "1_1") (pintype "passive"))
      (node (ref "R18") (pin "2") (pinfunction "2_2") (pintype "passive"))
      (node (ref "R5") (pin "2") (pinfunction "2_2") (pintype "passive"))
      (node (ref "R7") (pin "2") (pinfunction "2_2") (pintype "passive"))
      (node (ref "T1") (pin "2") (pinfunction "E_2") (pintype "passive"))
      (node (ref "TP1") (pin "P$1") (pinfunction "P$1_P$1") (pintype "bidirectional"))
      (node (ref "X1") (pin "2") (pinfunction "S_2") (pintype "passive"))
    )
    (net (code "11") (name "HV_IN") (class "Default")
      (node (ref "GDT1") (pin "P$1") (pinfunction "1_P$1") (pintype "bidirectional"))
      (node (ref "H1") (pin "B3,0") (pinfunction "MOUNT_B3,0") (pintype "passive"))
      (node (ref "Q1") (pin "1") (pinfunction "D_1") (pintype "passive"))
      (node (ref "Q1") (pin "2") (pinfunction "S_2") (pintype "passive"))
      (node (ref "Q3") (pin "3") (pinfunction "G_3") (pintype "passive"))
      (node (ref "R1") (pin "1") (pinfunction "1_1") (pintype "passive"))
      (node (ref "R2") (pin "1") (pinfunction "1_1") (pintype "passive"))
    )
    (net (code "12") (name "HV_OUT") (class "Default")
      (node (ref "D1") (pin "3") (pinfunction "C1A2_3") (pintype "passive"))
      (node (ref "GDT1") (pin "P$2") (pinfunction "2_P$2") (pintype "bidirectional"))
      (node (ref "H2") (pin "B3,0") (pinfunction "MOUNT_B3,0") (pintype "passive"))
      (node (ref "Q2") (pin "3") (pinfunction "G_3") (pintype "passive"))
      (node (ref "Q4") (pin "1") (pinfunction "D_1") (pintype "passive"))
      (node (ref "Q4") (pin "2") (pinfunction "S_2") (pintype "passive"))
      (node (ref "R1") (pin "2") (pinfunction "2_2") (pintype "passive"))
      (node (ref "R3") (pin "1") (pinfunction "1_1") (pintype "passive"))
    )
    (net (code "13") (name "Net-(B1-+)") (class "Default")
      (node (ref "B1") (pin "V+") (pinfunction "+_V+") (pintype "power_in"))
      (node (ref "S1") (pin "2") (pinfunction "2_2") (pintype "passive"))
      (node (ref "X1") (pin "1") (pinfunction "S_1") (pintype "passive"))
    )
    (net (code "14") (name "Net-(C6-Pad2)") (class "Default")
      (node (ref "C6") (pin "2") (pinfunction "2_2") (pintype "passive"))
      (node (ref "R16") (pin "1") (pinfunction "1_1") (pintype "passive"))
    )
    (net (code "15") (name "Net-(C24-Pad1)") (class "Default")
      (node (ref "C24") (pin "1") (pinfunction "1_1") (pintype "passive"))
      (node (ref "R35") (pin "1") (pinfunction "1_1") (pintype "passive"))
      (node (ref "R36") (pin "2") (pinfunction "2_2") (pintype "passive"))
    )
    (net (code "16") (name "Net-(C25-Pad2)") (class "Default")
      (node (ref "C25") (pin "2") (pinfunction "2_2") (pintype "passive"))
      (node (ref "R45") (pin "2") (pinfunction "2_2") (pintype "passive"))
    )
    (net (code "17") (name "Net-(D4-A1)") (class "Default")
      (node (ref "C5") (pin "1") (pinfunction "1_1") (pintype "passive"))
      (node (ref "D4") (pin "1") (pinfunction "A1_1") (pintype "passive"))
      (node (ref "IC5") (pin "4") (pinfunction "-IN_4") (pintype "input"))
      (node (ref "R10") (pin "2") (pinfunction "2_2") (pintype "passive"))
      (node (ref "T1") (pin "3") (pinfunction "C_3") (pintype "passive"))
    )
    (net (code "18") (name "Net-(D4-C1A2)") (class "Default")
      (node (ref "C7") (pin "1") (pinfunction "1_1") (pintype "passive"))
      (node (ref "D4") (pin "3") (pinfunction "C1A2_3") (pintype "passive"))
    )
    (net (code "19") (name "Net-(D6-A1)") (class "Default")
      (node (ref "D6") (pin "1") (pinfunction "A1_1") (pintype "passive"))
      (node (ref "IC4") (pin "1") (pinfunction "OUT_1") (pintype "output"))
      (node (ref "R14") (pin "2") (pinfunction "2_2") (pintype "passive"))
    )
    (net (code "20") (name "Net-(D6-C1A2)") (class "Default")
      (node (ref "D6") (pin "3") (pinfunction "C1A2_3") (pintype "passive"))
      (node (ref "R12") (pin "1") (pinfunction "1_1") (pintype "passive"))
    )
    (net (code "21") (name "Net-(D6-C2)") (class "Default")
      (node (ref "D6") (pin "2") (pinfunction "C2_2") (pintype "passive"))
      (node (ref "R11") (pin "1") (pinfunction "1_1") (pintype "passive"))
      (node (ref "R12") (pin "2") (pinfunction "2_2") (pintype "passive"))
    )
    (net (code "22") (name "Net-(D8-1(A))") (class "Default")
      (node (ref "D8") (pin "P$1") (pinfunction "1(A)_P$1") (pintype "passive"))
      (node (ref "R21") (pin "2") (pinfunction "2_2") (pintype "passive"))
    )
    (net (code "23") (name "Net-(D8-2(C))") (class "Default")
      (node (ref "C7") (pin "2") (pinfunction "2_2") (pintype "passive"))
      (node (ref "C8") (pin "2") (pinfunction "2_2") (pintype "passive"))
      (node (ref "D8") (pin "P$2") (pinfunction "2(C)_P$2") (pintype "passive"))
      (node (ref "IC5") (pin "8") (pinfunction "OUT_8") (pintype "output"))
      (node (ref "R20") (pin "1") (pinfunction "1_1") (pintype "passive"))
    )
    (net (code "24") (name "Net-(D9-C)") (class "Default")
      (node (ref "D9") (pin "1") (pinfunction "C_1") (pintype "passive"))
      (node (ref "IC7") (pin "3") (pinfunction "-IN_3") (pintype "input"))
      (node (ref "R27") (pin "2") (pinfunction "2_2") (pintype "passive"))
    )
    (net (code "25") (name "Net-(D10-PadA)") (class "Default")
      (node (ref "D10") (pin "A") (pinfunction "A_A") (pintype "passive"))
      (node (ref "R40") (pin "1") (pinfunction "1_1") (pintype "passive"))
      (node (ref "T2") (pin "E") (pinfunction "E_E") (pintype "passive"))
    )
    (net (code "26") (name "Net-(D12-A)") (class "Default")
      (node (ref "D12") (pin "2") (pinfunction "A_2") (pintype "passive"))
      (node (ref "R39") (pin "2") (pinfunction "2_2") (pintype "passive"))
      (node (ref "R42") (pin "2") (pinfunction "2_2") (pintype "passive"))
    )
    (net (code "27") (name "Net-(D13-PadA)") (class "Default")
      (node (ref "D13") (pin "A") (pinfunction "A_A") (pintype "passive"))
      (node (ref "Q6") (pin "E") (pinfunction "E_E") (pintype "passive"))
      (node (ref "R50") (pin "2") (pinfunction "2_2") (pintype "passive"))
      (node (ref "R52") (pin "1") (pinfunction "1_1") (pintype "passive"))
    )
    (net (code "28") (name "Net-(IC1-IN+)") (class "Default")
      (node (ref "IC1") (pin "3") (pinfunction "IN+_3") (pintype "input"))
      (node (ref "R2") (pin "2") (pinfunction "2_2") (pintype "passive"))
    )
    (net (code "29") (name "Net-(IC2-VI)") (class "Default")
      (node (ref "C1") (pin "1") (pinfunction "1_1") (pintype "passive"))
      (node (ref "C2") (pin "1") (pinfunction "1_1") (pintype "passive"))
      (node (ref "IC2") (pin "4") (pinfunction "VI_4") (pintype "input"))
      (node (ref "S1") (pin "1") (pinfunction "1_1") (pintype "passive"))
    )
    (net (code "30") (name "Net-(IC3-IN-)") (class "Default")
      (node (ref "IC3") (pin "2") (pinfunction "IN-_2") (pintype "input"))
      (node (ref "R5") (pin "1") (pinfunction "1_1") (pintype "passive"))
      (node (ref "R62") (pin "1") (pinfunction "A_1") (pintype "passive"))
    )
    (net (code "31") (name "Net-(IC3-OUT)") (class "Default")
      (node (ref "IC3") (pin "6") (pinfunction "OUT_6") (pintype "output"))
      (node (ref "R3") (pin "2") (pinfunction "2_2") (pintype "passive"))
      (node (ref "R4") (pin "2") (pinfunction "2_2") (pintype "passive"))
    )
    (net (code "32") (name "Net-(IC4A-+IN)") (class "Default")
      (node (ref "IC4") (pin "3") (pinfunction "+IN_3") (pintype "input"))
      (node (ref "R9") (pin "2") (pinfunction "2_2") (pintype "passive"))
    )
    (net (code "33") (name "Net-(IC4A--IN)") (class "Default")
      (node (ref "IC4") (pin "2") (pinfunction "-IN_2") (pintype "input"))
      (node (ref "R11") (pin "2") (pinfunction "2_2") (pintype "passive"))
      (node (ref "R7") (pin "1") (pinfunction "1_1") (pintype "passive"))
    )
    (net (code "34") (name "Net-(IC4B--IN)") (class "Default")
      (node (ref "C10") (pin "1") (pinfunction "1_1") (pintype "passive"))
      (node (ref "D7") (pin "A") (pinfunction "A_A") (pintype "passive"))
      (node (ref "IC4") (pin "6") (pinfunction "-IN_6") (pintype "input"))
      (node (ref "R20") (pin "2") (pinfunction "2_2") (pintype "passive"))
    )
    (net (code "35") (name "Net-(IC4B-OUT)") (class "Default")
      (node (ref "D3") (pin "A") (pinfunction "A_A") (pintype "passive"))
      (node (ref "IC4") (pin "7") (pinfunction "OUT_7") (pintype "output"))
      (node (ref "R8") (pin "1") (pinfunction "1_1") (pintype "passive"))
    )
    (net (code "36") (name "Net-(IC5-+IN)") (class "Default")
      (node (ref "C8") (pin "1") (pinfunction "1_1") (pintype "passive"))
      (node (ref "D3") (pin "C") (pinfunction "C_C") (pintype "passive"))
      (node (ref "D5") (pin "C") (pinfunction "C_C") (pintype "passive"))
      (node (ref "IC5") (pin "3") (pinfunction "+IN_3") (pintype "input"))
      (node (ref "R17") (pin "1") (pinfunction "1_1") (pintype "passive"))
    )
    (net (code "37") (name "Net-(IC5-HYST)") (class "Default")
      (node (ref "IC5") (pin "5") (pinfunction "HYST_5") (pintype "input"))
      (node (ref "R13") (pin "2") (pinfunction "2_2") (pintype "passive"))
      (node (ref "R15") (pin "1") (pinfunction "1_1") (pintype "passive"))
    )
    (net (code "38") (name "Net-(IC5-V+)") (class "Default")
      (node (ref "C9") (pin "1") (pinfunction "1_1") (pintype "passive"))
      (node (ref "IC5") (pin "7") (pinfunction "V+_7") (pintype "power_in"))
      (node (ref "Q5") (pin "1") (pinfunction "G_1") (pintype "passive"))
      (node (ref "R14") (pin "1") (pinfunction "1_1") (pintype "passive"))
    )
    (net (code "39") (name "Net-(IC6A-IN-)") (class "Default")
      (node (ref "C14") (pin "1") (pinfunction "1_1") (pintype "passive"))
      (node (ref "IC6") (pin "2") (pinfunction "IN-_2") (pintype "input"))
      (node (ref "PT1") (pin "P3") (pinfunction "COLLECTOR_P3") (pintype "passive"))
      (node (ref "R22") (pin "1") (pinfunction "1_1") (pintype "passive"))
    )
    (net (code "40") (name "Net-(IC6A-OUT)") (class "Default")
      (node (ref "C14") (pin "2") (pinfunction "2_2") (pintype "passive"))
      (node (ref "IC6") (pin "1") (pinfunction "OUT_1") (pintype "output"))
      (node (ref "R22") (pin "2") (pinfunction "2_2") (pintype "passive"))
      (node (ref "R23") (pin "1") (pinfunction "1_1") (pintype "passive"))
    )
    (net (code "41") (name "Net-(IC6B-IN+)") (class "Default")
      (node (ref "C17") (pin "1") (pinfunction "1_1") (pintype "passive"))
      (node (ref "IC6") (pin "5") (pinfunction "IN+_5") (pintype "input"))
      (node (ref "R23") (pin "2") (pinfunction "2_2") (pintype "passive"))
    )
    (net (code "42") (name "Net-(IC6B-IN-)") (class "Default")
      (node (ref "IC6") (pin "6") (pinfunction "IN-_6") (pintype "input"))
      (node (ref "R24") (pin "2") (pinfunction "2_2") (pintype "passive"))
      (node (ref "R25") (pin "1") (pinfunction "1_1") (pintype "passive"))
    )
    (net (code "43") (name "Net-(IC6B-OUT)") (class "Default")
      (node (ref "IC6") (pin "7") (pinfunction "OUT_7") (pintype "output"))
      (node (ref "R24") (pin "1") (pinfunction "1_1") (pintype "passive"))
      (node (ref "R26") (pin "1") (pinfunction "1_1") (pintype "passive"))
    )
    (net (code "44") (name "Net-(IC7-+IN)") (class "Default")
      (node (ref "IC7") (pin "2") (pinfunction "+IN_2") (pintype "input"))
      (node (ref "R26") (pin "2") (pinfunction "2_2") (pintype "passive"))
      (node (ref "R28") (pin "1") (pinfunction "1_1") (pintype "passive"))
    )
    (net (code "45") (name "Net-(IC7-OUT)") (class "Default")
      (node (ref "IC7") (pin "7") (pinfunction "OUT_7") (pintype "output"))
      (node (ref "R28") (pin "2") (pinfunction "2_2") (pintype "passive"))
      (node (ref "R29") (pin "2") (pinfunction "2_2") (pintype "passive"))
      (node (ref "R30") (pin "1") (pinfunction "1_1") (pintype "passive"))
      (node (ref "R31") (pin "1") (pinfunction "1_1") (pintype "passive"))
    )
    (net (code "46") (name "Net-(IC8A-CLR)") (class "Default")
      (node (ref "IC8") (pin "1") (pinfunction "CLR_1") (pintype "input"))
      (node (ref "IC8") (pin "13") (pinfunction "CLR_13") (pintype "input"))
      (node (ref "IC9") (pin "4") (pinfunction "O_4") (pintype "output"))
    )
    (net (code "47") (name "Net-(IC8A-D)") (class "Default")
      (node (ref "IC8") (pin "10") (pinfunction "PRE_10") (pintype "input"))
      (node (ref "IC8") (pin "12") (pinfunction "D_12") (pintype "input"))
      (node (ref "IC8") (pin "2") (pinfunction "D_2") (pintype "input"))
      (node (ref "IC8") (pin "4") (pinfunction "PRE_4") (pintype "input"))
      (node (ref "R34") (pin "1") (pinfunction "1_1") (pintype "passive"))
    )
    (net (code "48") (name "Net-(IC8B-Q)") (class "Default")
      (node (ref "IC8") (pin "9") (pinfunction "Q_9") (pintype "output"))
      (node (ref "IC9") (pin "2") (pinfunction "I1_2") (pintype "input"))
    )
    (net (code "49") (name "Net-(IC10-IN+)") (class "Default")
      (node (ref "C22") (pin "2") (pinfunction "2_2") (pintype "passive"))
      (node (ref "IC10") (pin "3") (pinfunction "IN+_3") (pintype "input"))
      (node (ref "R35") (pin "2") (pinfunction "2_2") (pintype "passive"))
    )
    (net (code "50") (name "Net-(IC10-IN-)") (class "Default")
      (node (ref "C23") (pin "1") (pinfunction "1_1") (pintype "passive"))
      (node (ref "IC10") (pin "2") (pinfunction "IN-_2") (pintype "input"))
      (node (ref "R37") (pin "2") (pinfunction "2_2") (pintype "passive"))
    )
    (net (code "51") (name "Net-(IC10-OUT)") (class "Default")
      (node (ref "C23") (pin "2") (pinfunction "2_2") (pintype "passive"))
      (node (ref "C24") (pin "2") (pinfunction "2_2") (pintype "passive"))
      (node (ref "IC10") (pin "6") (pinfunction "OUT_6") (pintype "output"))
      (node (ref "R37") (pin "1") (pinfunction "1_1") (pintype "passive"))
      (node (ref "R38") (pin "2") (pinfunction "2_2") (pintype "passive"))
      (node (ref "R46") (pin "1") (pinfunction "1_1") (pintype "passive"))
    )
    (net (code "52") (name "Net-(IC11A-I)") (class "Default")
      (node (ref "IC11") (pin "2") (pinfunction "I_2") (pintype "input"))
      (node (ref "IC8") (pin "5") (pinfunction "Q_5") (pintype "output"))
      (node (ref "IC9") (pin "1") (pinfunction "I0_1") (pintype "input"))
    )
    (net (code "53") (name "Net-(IC12A-I)") (class "Default")
      (node (ref "IC12") (pin "2") (pinfunction "I_2") (pintype "input"))
      (node (ref "IC8") (pin "8") (pinfunction "~{Q}_8") (pintype "output"))
    )
    (net (code "54") (name "Net-(IC13A-I)") (class "Default")
      (node (ref "IC13") (pin "2") (pinfunction "I_2") (pintype "input"))
      (node (ref "IC16") (pin "1") (pinfunction "FOUT_1") (pintype "open_collector"))
      (node (ref "R61") (pin "1") (pinfunction "1_1") (pintype "passive"))
    )
    (net (code "55") (name "Net-(IC14-IN-)") (class "Default")
      (node (ref "IC14") (pin "2") (pinfunction "IN-_2") (pintype "input"))
      (node (ref "R46") (pin "2") (pinfunction "2_2") (pintype "passive"))
      (node (ref "R47") (pin "2") (pinfunction "2_2") (pintype "passive"))
      (node (ref "R51") (pin "1") (pinfunction "1_1") (pintype "passive"))
    )
    (net (code "56") (name "Net-(IC14-OUT)") (class "Default")
      (node (ref "IC14") (pin "6") (pinfunction "OUT_6") (pintype "output"))
      (node (ref "R51") (pin "2") (pinfunction "2_2") (pintype "passive"))
      (node (ref "R54") (pin "1") (pinfunction "1_1") (pintype "passive"))
    )
    (net (code "57") (name "Net-(IC15-IN-)") (class "Default")
      (node (ref "IC15") (pin "2") (pinfunction "IN-_2") (pintype "input"))
      (node (ref "R54") (pin "2") (pinfunction "2_2") (pintype "passive"))
      (node (ref "R55") (pin "1") (pinfunction "A_1") (pintype "passive"))
      (node (ref "R55") (pin "2") (pinfunction "S_2") (pintype "passive"))
    )
    (net (code "58") (name "Net-(IC15-OUT)") (class "Default")
      (node (ref "IC15") (pin "6") (pinfunction "OUT_6") (pintype "output"))
      (node (ref "R58") (pin "2") (pinfunction "2_2") (pintype "passive"))
      (node (ref "R59") (pin "1") (pinfunction "1_1") (pintype "passive"))
      (node (ref "R60") (pin "1") (pinfunction "1_1") (pintype "passive"))
    )
    (net (code "59") (name "Net-(IC16-CT1)") (class "Default")
      (node (ref "C26") (pin "1") (pinfunction "1_1") (pintype "passive"))
      (node (ref "IC16") (pin "6") (pinfunction "CT1_6") (pintype "passive"))
    )
    (net (code "60") (name "Net-(IC16-CT2)") (class "Default")
      (node (ref "C26") (pin "2") (pinfunction "2_2") (pintype "passive"))
      (node (ref "IC16") (pin "7") (pinfunction "CT2_7") (pintype "passive"))
    )
    (net (code "61") (name "Net-(IC16-RT)") (class "Default")
      (node (ref "IC16") (pin "3") (pinfunction "RT_3") (pintype "passive"))
      (node (ref "R56") (pin "2") (pinfunction "2_2") (pintype "passive"))
    )
    (net (code "62") (name "Net-(LED1-PadA)") (class "Default")
      (node (ref "LED1") (pin "A") (pinfunction "A_A") (pintype "passive"))
      (node (ref "R30") (pin "2") (pinfunction "2_2") (pintype "passive"))
    )
    (net (code "63") (name "Net-(LED2-PadA)") (class "Default")
      (node (ref "LED2") (pin "A") (pinfunction "A_A") (pintype "passive"))
      (node (ref "R32") (pin "2") (pinfunction "2_2") (pintype "passive"))
    )
    (net (code "64") (name "Net-(LED3-PadC)") (class "Default")
      (node (ref "LED3") (pin "C") (pinfunction "C_C") (pintype "passive"))
      (node (ref "R33") (pin "2") (pinfunction "2_2") (pintype "passive"))
    )
    (net (code "65") (name "Net-(LED4-PadC)") (class "Default")
      (node (ref "LED4") (pin "C") (pinfunction "C_C") (pintype "passive"))
      (node (ref "R44") (pin "2") (pinfunction "2_2") (pintype "passive"))
      (node (ref "T2") (pin "B") (pinfunction "B_B") (pintype "passive"))
    )
    (net (code "66") (name "Net-(LED6-PadA)") (class "Default")
      (node (ref "LED6") (pin "A") (pinfunction "A_A") (pintype "passive"))
      (node (ref "R59") (pin "2") (pinfunction "2_2") (pintype "passive"))
    )
    (net (code "67") (name "Net-(Q1-G)") (class "Default")
      (node (ref "Q1") (pin "3") (pinfunction "G_3") (pintype "passive"))
      (node (ref "Q2") (pin "1") (pinfunction "D_1") (pintype "passive"))
      (node (ref "Q2") (pin "2") (pinfunction "S_2") (pintype "passive"))
      (node (ref "Q3") (pin "1") (pinfunction "D_1") (pintype "passive"))
      (node (ref "Q3") (pin "2") (pinfunction "S_2") (pintype "passive"))
      (node (ref "Q4") (pin "3") (pinfunction "G_3") (pintype "passive"))
    )
    (net (code "68") (name "Net-(Q6-PadB)") (class "Default")
      (node (ref "Q6") (pin "B") (pinfunction "B_B") (pintype "passive"))
      (node (ref "R48") (pin "2") (pinfunction "2_2") (pintype "passive"))
    )
    (net (code "69") (name "Net-(Q6-PadC)") (class "Default")
      (node (ref "Q6") (pin "C") (pinfunction "C_C") (pintype "passive"))
      (node (ref "R49") (pin "1") (pinfunction "1_1") (pintype "passive"))
    )
    (net (code "70") (name "Net-(R6-A)") (class "Default")
      (node (ref "R10") (pin "1") (pinfunction "1_1") (pintype "passive"))
      (node (ref "R6") (pin "1") (pinfunction "A_1") (pintype "passive"))
      (node (ref "R6") (pin "2") (pinfunction "S_2") (pintype "passive"))
    )
    (net (code "71") (name "Net-(R17-Pad2)") (class "Default")
      (node (ref "R17") (pin "2") (pinfunction "2_2") (pintype "passive"))
      (node (ref "R18") (pin "1") (pinfunction "1_1") (pintype "passive"))
      (node (ref "R19") (pin "1") (pinfunction "1_1") (pintype "passive"))
    )
    (net (code "72") (name "Net-(R43-E)") (class "Default")
      (node (ref "R42") (pin "1") (pinfunction "1_1") (pintype "passive"))
      (node (ref "R43") (pin "3") (pinfunction "E_3") (pintype "passive"))
    )
    (net (code "73") (name "Net-(R43-S)") (class "Default")
      (node (ref "R43") (pin "2") (pinfunction "S_2") (pintype "passive"))
      (node (ref "R47") (pin "1") (pinfunction "1_1") (pintype "passive"))
    )
    (net (code "74") (name "Net-(R55-E)") (class "Default")
      (node (ref "R55") (pin "3") (pinfunction "E_3") (pintype "passive"))
      (node (ref "R58") (pin "1") (pinfunction "1_1") (pintype "passive"))
    )
    (net (code "75") (name "Net-(R57-E)") (class "Default")
      (node (ref "R56") (pin "1") (pinfunction "1_1") (pintype "passive"))
      (node (ref "R57") (pin "3") (pinfunction "E_3") (pintype "passive"))
    )
    (net (code "76") (name "Net-(R62-E)") (class "Default")
      (node (ref "R4") (pin "1") (pinfunction "1_1") (pintype "passive"))
      (node (ref "R62") (pin "2") (pinfunction "S_2") (pintype "passive"))
      (node (ref "R62") (pin "3") (pinfunction "E_3") (pintype "passive"))
    )
    (net (code "77") (name "Net-(T1-B)") (class "Default")
      (node (ref "R8") (pin "2") (pinfunction "2_2") (pintype "passive"))
      (node (ref "T1") (pin "1") (pinfunction "B_1") (pintype "passive"))
    )
    (net (code "78") (name "Net-(T3-B)") (class "Default")
      (node (ref "LED5") (pin "A") (pinfunction "A_A") (pintype "passive"))
      (node (ref "R44") (pin "1") (pinfunction "1_1") (pintype "passive"))
      (node (ref "T3") (pin "1") (pinfunction "B_1") (pintype "passive"))
    )
    (net (code "79") (name "Net-(T3-C)") (class "Default")
      (node (ref "C25") (pin "1") (pinfunction "1_1") (pintype "passive"))
      (node (ref "R48") (pin "1") (pinfunction "1_1") (pintype "passive"))
      (node (ref "T2") (pin "C") (pinfunction "C_C") (pintype "passive"))
      (node (ref "T3") (pin "3") (pinfunction "C_3") (pintype "passive"))
    )
    (net (code "80") (name "Net-(T3-E)") (class "Default")
      (node (ref "D11") (pin "C") (pinfunction "C_C") (pintype "passive"))
      (node (ref "R41") (pin "2") (pinfunction "2_2") (pintype "passive"))
      (node (ref "T3") (pin "2") (pinfunction "E_2") (pintype "passive"))
    )
    (net (code "81") (name "PE") (class "Default")
      (node (ref "H10") (pin "B3,0") (pinfunction "MOUNT_B3,0") (pintype "passive"))
      (node (ref "H9") (pin "B3,0") (pinfunction "MOUNT_B3,0") (pintype "passive"))
      (node (ref "X3") (pin "1") (pinfunction "1_1") (pintype "passive"))
      (node (ref "X3") (pin "3") (pinfunction "3_3") (pintype "passive"))
      (node (ref "X3") (pin "5") (pinfunction "5_5") (pintype "passive"))
      (node (ref "X3") (pin "7") (pinfunction "7_7") (pintype "passive"))
      (node (ref "X3") (pin "S1") (pinfunction "S1_S1") (pintype "passive"))
      (node (ref "X3") (pin "S2") (pinfunction "S2_S2") (pintype "passive"))
      (node (ref "X4") (pin "3") (pinfunction "S_3") (pintype "passive"))
    )
    (net (code "82") (name "PLL_OUT") (class "Default")
      (node (ref "IC13") (pin "4") (pinfunction "O_4") (pintype "output"))
      (node (ref "IC8") (pin "3") (pinfunction "CLK_3") (pintype "input"))
    )
    (net (code "83") (name "V+") (class "Default")
      (node (ref "C15") (pin "1") (pinfunction "1_1") (pintype "passive"))
      (node (ref "C16") (pin "1") (pinfunction "1_1") (pintype "passive"))
      (node (ref "C18") (pin "1") (pinfunction "1_1") (pintype "passive"))
      (node (ref "C20") (pin "1") (pinfunction "1_1") (pintype "passive"))
      (node (ref "C27") (pin "1") (pinfunction "1_1") (pintype "passive"))
      (node (ref "C28") (pin "1") (pinfunction "1_1") (pintype "passive"))
      (node (ref "C29") (pin "1") (pinfunction "1_1") (pintype "passive"))
      (node (ref "C30") (pin "1") (pinfunction "1_1") (pintype "passive"))
      (node (ref "C31") (pin "2") (pinfunction "2_2") (pintype "passive"))
      (node (ref "C33") (pin "1") (pinfunction "1_1") (pintype "passive"))
      (node (ref "C34") (pin "2") (pinfunction "2_2") (pintype "passive"))
      (node (ref "C36") (pin "1") (pinfunction "1_1") (pintype "passive"))
      (node (ref "C37") (pin "1") (pinfunction "1_1") (pintype "passive"))
      (node (ref "IC10") (pin "7") (pinfunction "+VS_7") (pintype "input"))
      (node (ref "IC11") (pin "5") (pinfunction "VCC_5") (pintype "power_in"))
      (node (ref "IC12") (pin "5") (pinfunction "VCC_5") (pintype "power_in"))
      (node (ref "IC13") (pin "5") (pinfunction "VCC_5") (pintype "power_in"))
      (node (ref "IC14") (pin "7") (pinfunction "+VS_7") (pintype "input"))
      (node (ref "IC15") (pin "7") (pinfunction "+VS_7") (pintype "input"))
      (node (ref "IC16") (pin "8") (pinfunction "+VS_8") (pintype "power_in"))
      (node (ref "IC6") (pin "8") (pinfunction "V+_8") (pintype "power_in"))
      (node (ref "IC7") (pin "8") (pinfunction "V+_8") (pintype "power_in"))
      (node (ref "IC8") (pin "14") (pinfunction "VCC_14") (pintype "power_in"))
      (node (ref "IC9") (pin "5") (pinfunction "VCC_5") (pintype "power_in"))
      (node (ref "LED4") (pin "A") (pinfunction "A_A") (pintype "passive"))
      (node (ref "R27") (pin "1") (pinfunction "1_1") (pintype "passive"))
      (node (ref "R29") (pin "1") (pinfunction "1_1") (pintype "passive"))
      (node (ref "R32") (pin "1") (pinfunction "1_1") (pintype "passive"))
      (node (ref "R34") (pin "2") (pinfunction "2_2") (pintype "passive"))
      (node (ref "R40") (pin "2") (pinfunction "2_2") (pintype "passive"))
      (node (ref "R49") (pin "2") (pinfunction "2_2") (pintype "passive"))
      (node (ref "R61") (pin "2") (pinfunction "2_2") (pintype "passive"))
      (node (ref "X2") (pin "2") (pinfunction "2_2") (pintype "passive"))
    )
    (net (code "84") (name "V-") (class "Default")
      (node (ref "C19") (pin "2") (pinfunction "2_2") (pintype "passive"))
      (node (ref "C21") (pin "2") (pinfunction "2_2") (pintype "passive"))
      (node (ref "C32") (pin "1") (pinfunction "1_1") (pintype "passive"))
      (node (ref "C35") (pin "1") (pinfunction "1_1") (pintype "passive"))
      (node (ref "IC14") (pin "4") (pinfunction "-VS_4") (pintype "input"))
      (node (ref "IC15") (pin "4") (pinfunction "-VS_4") (pintype "input"))
      (node (ref "PT1") (pin "P4") (pinfunction "BASE_P4") (pintype "passive"))
      (node (ref "PT1") (pin "P5") (pinfunction "EMITTER_P5") (pintype "passive"))
      (node (ref "R33") (pin "1") (pinfunction "1_1") (pintype "passive"))
      (node (ref "R39") (pin "1") (pinfunction "1_1") (pintype "passive"))
      (node (ref "X2") (pin "8") (pinfunction "8_8") (pintype "passive"))
    )
    (net (code "85") (name "VDD") (class "Default")
      (node (ref "X3") (pin "2") (pinfunction "2_2") (pintype "passive"))
      (node (ref "X4") (pin "1") (pinfunction "S_1") (pintype "passive"))
    )
    (net (code "86") (name "VGUARD") (class "Default")
      (node (ref "D2") (pin "3") (pinfunction "C1A2_3") (pintype "passive"))
      (node (ref "IC1") (pin "2") (pinfunction "IN-_2") (pintype "input"))
      (node (ref "IC1") (pin "6") (pinfunction "OUT_6") (pintype "output"))
      (node (ref "R6") (pin "3") (pinfunction "E_3") (pintype "passive"))
    )
    (net (code "87") (name "VREF") (class "Default")
      (node (ref "D7") (pin "C") (pinfunction "C_C") (pintype "passive"))
      (node (ref "IC3") (pin "3") (pinfunction "IN+_3") (pintype "input"))
      (node (ref "IC4") (pin "5") (pinfunction "+IN_5") (pintype "input"))
      (node (ref "IC5") (pin "6") (pinfunction "VREF_6") (pintype "passive"))
      (node (ref "Q5") (pin "3") (pinfunction "D_3") (pintype "passive"))
      (node (ref "R15") (pin "2") (pinfunction "2_2") (pintype "passive"))
      (node (ref "R16") (pin "2") (pinfunction "2_2") (pintype "passive"))
      (node (ref "R19") (pin "2") (pinfunction "2_2") (pintype "passive"))
      (node (ref "R9") (pin "1") (pinfunction "1_1") (pintype "passive"))
    )
    (net (code "88") (name "VSS") (class "Default")
      (node (ref "X3") (pin "8") (pinfunction "8_8") (pintype "passive"))
      (node (ref "X4") (pin "5") (pinfunction "S_5") (pintype "passive"))
    )
    (net (code "89") (name "unconnected-(D16-C1A2-Pad3)") (class "Default")
      (node (ref "D16") (pin "3") (pinfunction "C1A2_3") (pintype "passive"))
    )
    (net (code "90") (name "unconnected-(IC7-ON-Pad5)") (class "Default")
      (node (ref "IC7") (pin "5") (pinfunction "ON_5") (pintype "passive"))
    )
    (net (code "91") (name "unconnected-(IC7-ON{slash}STR-Pad6)") (class "Default")
      (node (ref "IC7") (pin "6") (pinfunction "ON/STR_6") (pintype "passive"))
    )
    (net (code "92") (name "unconnected-(IC8A-~{Q}-Pad6)") (class "Default")
      (node (ref "IC8") (pin "6") (pinfunction "~{Q}_6") (pintype "output"))
    )
  )
)
